# rgb-led_alt.net
KiCad netlist of a schematic drawn in EAGLE
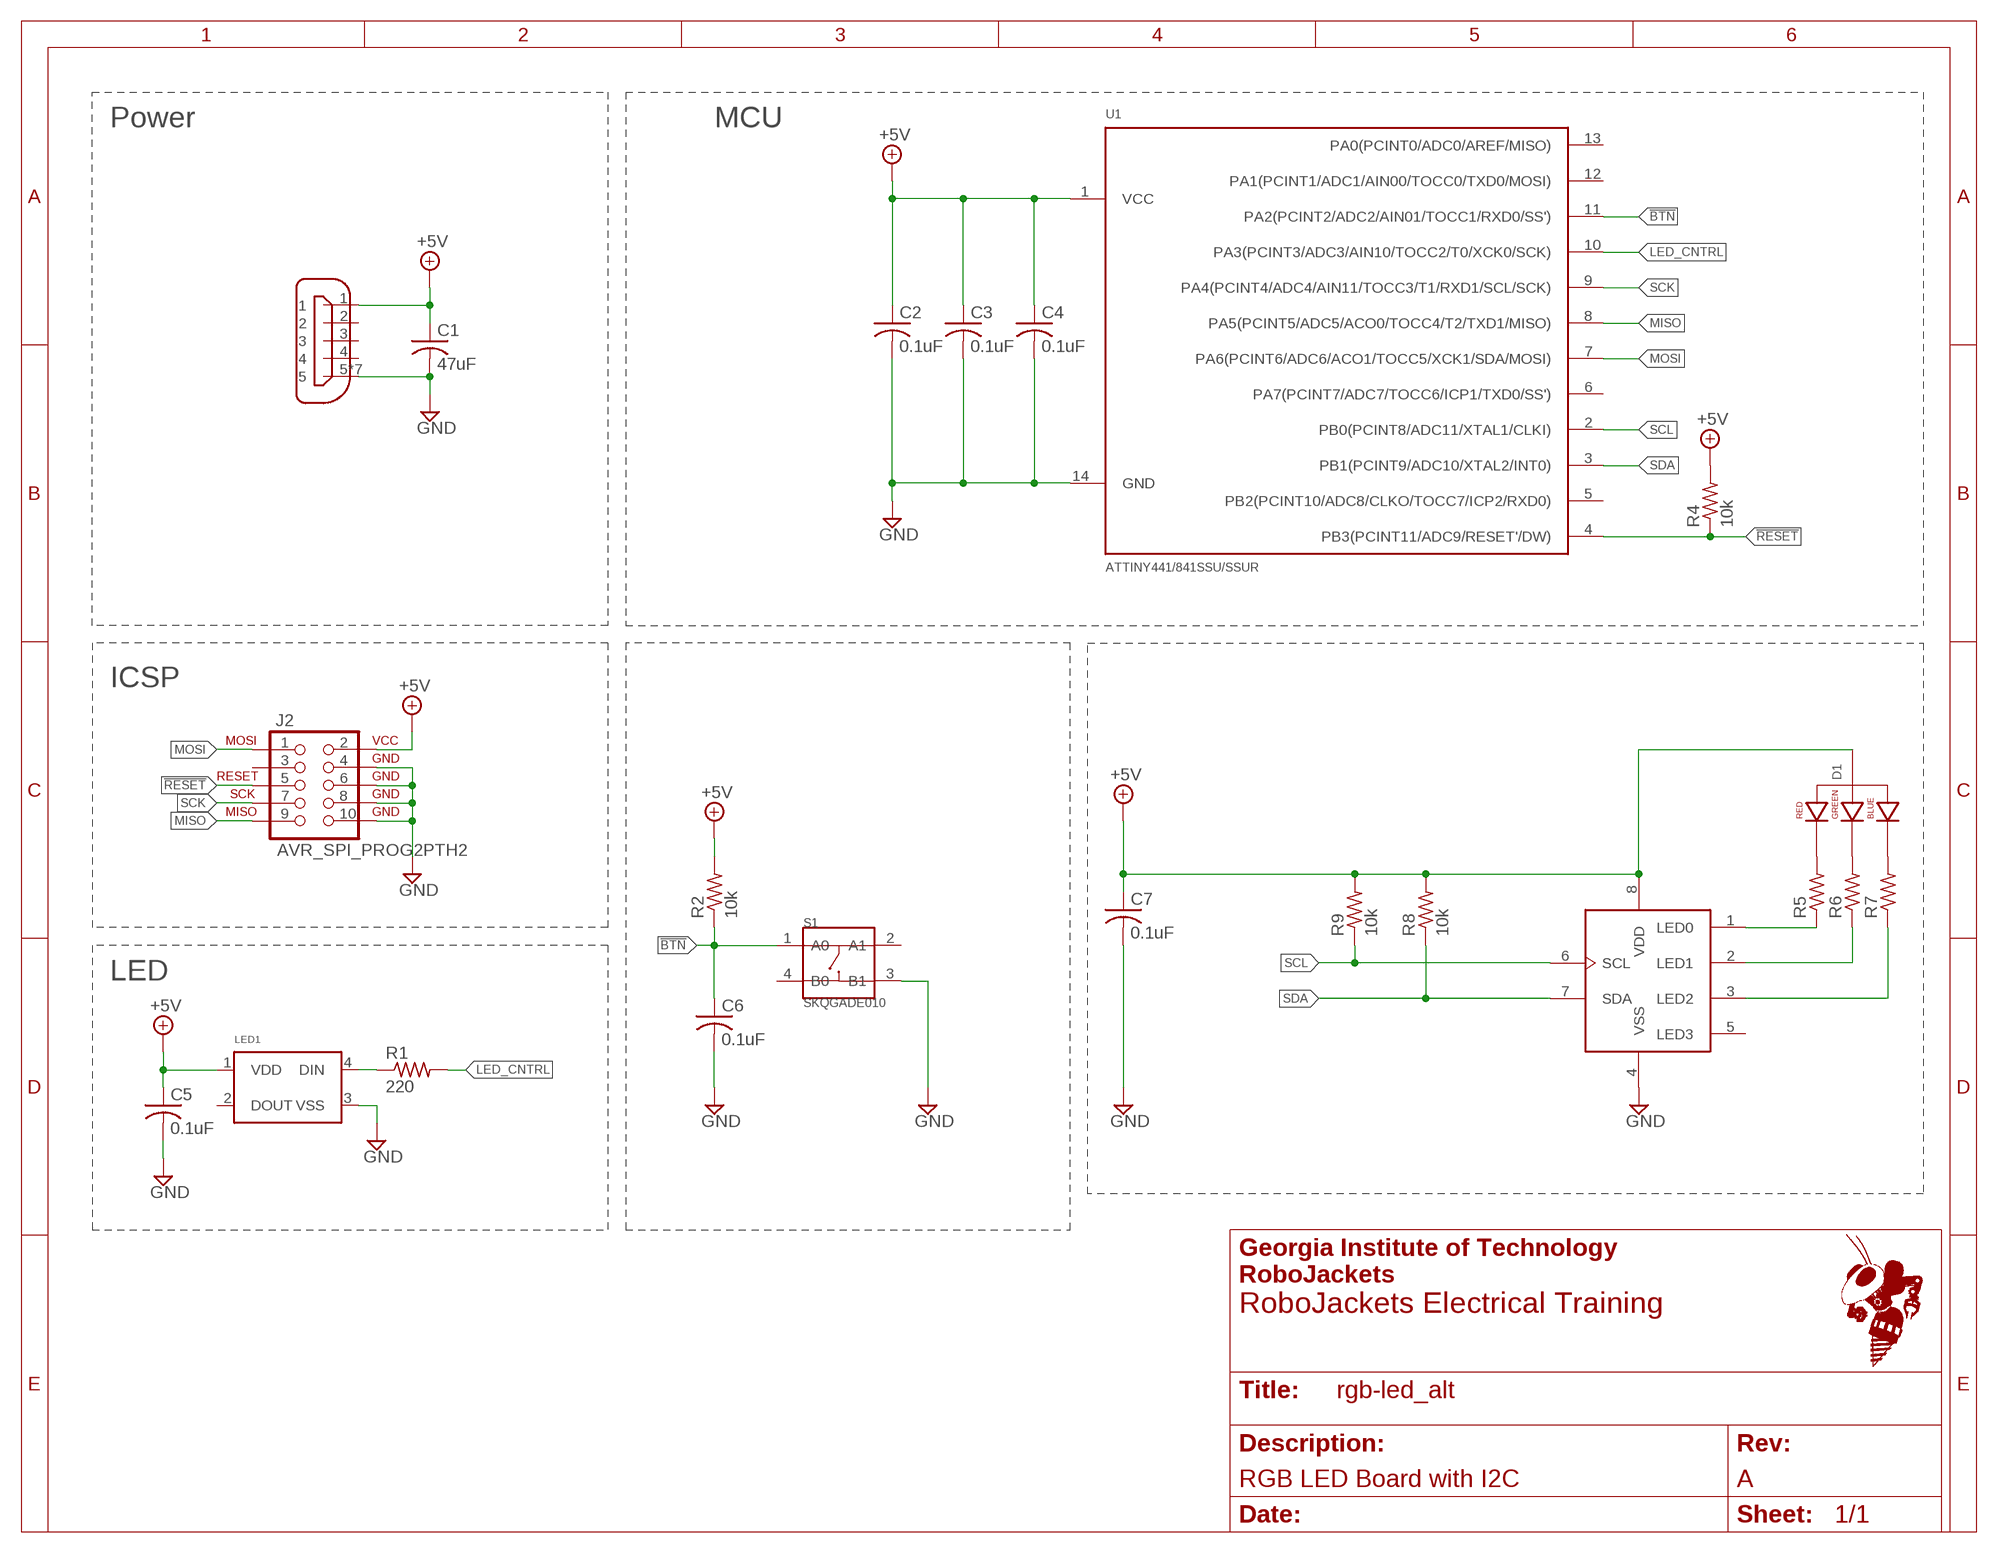
[diagram p0: schematic, sheet 1]

(export (version "E")
  (design (tool "Eeschema 10.0.6"))
  (components
    (comp (ref "C1")
      (value "47uF")
      (footprint "eagle-import:C1206")
      (libsource (lib "eagle-import") (part "C-USC1206"))
    )
    (comp (ref "C2")
      (value "0.1uF")
      (footprint "eagle-import:C0603")
      (libsource (lib "eagle-import") (part "C-USC0603"))
    )
    (comp (ref "C3")
      (value "0.1uF")
      (footprint "eagle-import:C0603")
      (libsource (lib "eagle-import") (part "C-USC0603"))
    )
    (comp (ref "C4")
      (value "0.1uF")
      (footprint "eagle-import:C0603")
      (libsource (lib "eagle-import") (part "C-USC0603"))
    )
    (comp (ref "C5")
      (value "0.1uF")
      (footprint "eagle-import:C0603")
      (libsource (lib "eagle-import") (part "C-USC0603"))
    )
    (comp (ref "C6")
      (value "0.1uF")
      (footprint "eagle-import:C0603")
      (libsource (lib "eagle-import") (part "C-USC0603"))
    )
    (comp (ref "C7")
      (value "0.1uF")
      (footprint "eagle-import:C0603")
      (libsource (lib "eagle-import") (part "C-USC0603"))
    )
    (comp (ref "D1")
      (value "LED-RGB-CA-THRUCLEAR")
      (footprint "eagle-import:LED-RGB-THRU")
      (libsource (lib "eagle-import") (part "LED-RGB-CA-THRUCLEAR"))
    )
    (comp (ref "J1")
      (value "MICRO-USB")
      (footprint "eagle-import:GS-14-2180")
      (libsource (lib "eagle-import") (part "MICRO-USB"))
    )
    (comp (ref "J2")
      (value "AVR_SPI_PROG2PTH2")
      (footprint "eagle-import:2X5-SHROUDED")
      (libsource (lib "eagle-import") (part "AVR_SPI_PROG2PTH2"))
    )
    (comp (ref "LED1")
      (value "WS2812B")
      (footprint "eagle-import:5050")
      (libsource (lib "eagle-import") (part "WS2812B"))
    )
    (comp (ref "R1")
      (value "220")
      (footprint "eagle-import:R0603")
      (libsource (lib "eagle-import") (part "R-US_R0603"))
    )
    (comp (ref "R2")
      (value "10k")
      (footprint "eagle-import:R0603")
      (libsource (lib "eagle-import") (part "resistor_R-US_R0603"))
    )
    (comp (ref "R4")
      (value "10k")
      (footprint "eagle-import:R0603")
      (libsource (lib "eagle-import") (part "resistor_R-US_R0603"))
    )
    (comp (ref "R5")
      (value "R-US_R0603")
      (footprint "eagle-import:R0603")
      (libsource (lib "eagle-import") (part "resistor_R-US_R0603"))
    )
    (comp (ref "R6")
      (value "R-US_R0603")
      (footprint "eagle-import:R0603")
      (libsource (lib "eagle-import") (part "resistor_R-US_R0603"))
    )
    (comp (ref "R7")
      (value "R-US_R0603")
      (footprint "eagle-import:R0603")
      (libsource (lib "eagle-import") (part "resistor_R-US_R0603"))
    )
    (comp (ref "R8")
      (value "10k")
      (footprint "eagle-import:R0603")
      (libsource (lib "eagle-import") (part "resistor_R-US_R0603"))
    )
    (comp (ref "R9")
      (value "10k")
      (footprint "eagle-import:R0603")
      (libsource (lib "eagle-import") (part "resistor_R-US_R0603"))
    )
    (comp (ref "S1")
      (value "SKQGADE010")
      (footprint "eagle-import:SW4-SMD-5.2X5.2X1.5MM")
      (libsource (lib "eagle-import") (part "SMD-SWITCH-TOP-260GF(4P-D5.2MM)"))
    )
    (comp (ref "U1")
      (value "ATTINY441/841SSU/SSUR")
      (footprint "eagle-import:SOIC-14")
      (libsource (lib "eagle-import") (part "ATTINY441/841SSU/SSUR"))
    )
    (comp (ref "U2")
      (value "PCA9533")
      (footprint "eagle-import:SOIC8")
      (libsource (lib "eagle-import") (part "PCA9533"))
    )
  )
  (nets
    (net (code "1") (name "+5V") (class "Default")
      (node (ref "C1") (pin "1") (pinfunction "1_1") (pintype "passive"))
      (node (ref "C2") (pin "1") (pinfunction "1_1") (pintype "passive"))
      (node (ref "C3") (pin "1") (pinfunction "1_1") (pintype "passive"))
      (node (ref "C4") (pin "1") (pinfunction "1_1") (pintype "passive"))
      (node (ref "C5") (pin "1") (pinfunction "1_1") (pintype "passive"))
      (node (ref "C7") (pin "1") (pinfunction "1_1") (pintype "passive"))
      (node (ref "D1") (pin "2") (pinfunction "ANODE_2") (pintype "bidirectional"))
      (node (ref "J1") (pin "1") (pinfunction "1_1") (pintype "bidirectional"))
      (node (ref "J2") (pin "2") (pinfunction "VCC_2") (pintype "power_in"))
      (node (ref "LED1") (pin "1") (pinfunction "VDD_1") (pintype "bidirectional"))
      (node (ref "R2") (pin "2") (pinfunction "2_2") (pintype "passive"))
      (node (ref "R4") (pin "2") (pinfunction "2_2") (pintype "passive"))
      (node (ref "R8") (pin "2") (pinfunction "2_2") (pintype "passive"))
      (node (ref "R9") (pin "2") (pinfunction "2_2") (pintype "passive"))
      (node (ref "U1") (pin "1") (pinfunction "VCC_1") (pintype "bidirectional"))
      (node (ref "U2") (pin "8") (pinfunction "VDD_8") (pintype "power_in"))
    )
    (net (code "2") (name "/~{BTN}") (class "Default")
      (node (ref "C6") (pin "1") (pinfunction "1_1") (pintype "passive"))
      (node (ref "R2") (pin "1") (pinfunction "1_1") (pintype "passive"))
      (node (ref "S1") (pin "1") (pinfunction "A0_1") (pintype "bidirectional"))
      (node (ref "U1") (pin "11") (pinfunction "PA2(PCINT2/ADC2/AIN01/TOCC1/RXD0/SS')_11") (pintype "bidirectional"))
    )
    (net (code "3") (name "/~{RESET}") (class "Default")
      (node (ref "J2") (pin "5") (pinfunction "RESET_5") (pintype "passive"))
      (node (ref "R4") (pin "1") (pinfunction "1_1") (pintype "passive"))
      (node (ref "U1") (pin "4") (pinfunction "PB3(PCINT11/ADC9/RESET'/DW)_4") (pintype "bidirectional"))
    )
    (net (code "4") (name "GND") (class "Default")
      (node (ref "C1") (pin "2") (pinfunction "2_2") (pintype "passive"))
      (node (ref "C2") (pin "2") (pinfunction "2_2") (pintype "passive"))
      (node (ref "C3") (pin "2") (pinfunction "2_2") (pintype "passive"))
      (node (ref "C4") (pin "2") (pinfunction "2_2") (pintype "passive"))
      (node (ref "C5") (pin "2") (pinfunction "2_2") (pintype "passive"))
      (node (ref "C6") (pin "2") (pinfunction "2_2") (pintype "passive"))
      (node (ref "C7") (pin "2") (pinfunction "2_2") (pintype "passive"))
      (node (ref "J1") (pin "5") (pinfunction "5_5") (pintype "bidirectional"))
      (node (ref "J1") (pin "5@1") (pinfunction "5_5@1") (pintype "bidirectional"))
      (node (ref "J1") (pin "5@2") (pinfunction "5_5@2") (pintype "bidirectional"))
      (node (ref "J1") (pin "5@3") (pinfunction "5_5@3") (pintype "bidirectional"))
      (node (ref "J1") (pin "5@4") (pinfunction "5_5@4") (pintype "bidirectional"))
      (node (ref "J1") (pin "5@6") (pinfunction "5_5@6") (pintype "bidirectional"))
      (node (ref "J1") (pin "5@7") (pinfunction "5_5@7") (pintype "bidirectional"))
      (node (ref "J2") (pin "10") (pinfunction "GND_10") (pintype "power_in"))
      (node (ref "J2") (pin "4") (pinfunction "GND_4") (pintype "power_in"))
      (node (ref "J2") (pin "6") (pinfunction "GND_6") (pintype "power_in"))
      (node (ref "J2") (pin "8") (pinfunction "GND_8") (pintype "power_in"))
      (node (ref "LED1") (pin "3") (pinfunction "VSS_3") (pintype "bidirectional"))
      (node (ref "S1") (pin "3") (pinfunction "B1_3") (pintype "bidirectional"))
      (node (ref "U1") (pin "14") (pinfunction "GND_14") (pintype "bidirectional"))
      (node (ref "U2") (pin "4") (pinfunction "VSS_4") (pintype "power_in"))
    )
    (net (code "5") (name "LED_CNTRL") (class "Default")
      (node (ref "R1") (pin "2") (pinfunction "2_2") (pintype "passive"))
      (node (ref "U1") (pin "10") (pinfunction "PA3(PCINT3/ADC3/AIN10/TOCC2/T0/XCK0/SCK)_10") (pintype "bidirectional"))
    )
    (net (code "6") (name "MISO") (class "Default")
      (node (ref "J2") (pin "9") (pinfunction "MISO_9") (pintype "passive"))
      (node (ref "U1") (pin "8") (pinfunction "PA5(PCINT5/ADC5/ACO0/TOCC4/T2/TXD1/MISO)_8") (pintype "bidirectional"))
    )
    (net (code "7") (name "MOSI") (class "Default")
      (node (ref "J2") (pin "1") (pinfunction "MOSI_1") (pintype "passive"))
      (node (ref "U1") (pin "7") (pinfunction "PA6(PCINT6/ADC6/ACO1/TOCC5/XCK1/SDA/MOSI)_7") (pintype "bidirectional"))
    )
    (net (code "8") (name "Net-(D1-BLUE_CATHODE)") (class "Default")
      (node (ref "D1") (pin "4") (pinfunction "BLUE_CATHODE_4") (pintype "bidirectional"))
      (node (ref "R7") (pin "2") (pinfunction "2_2") (pintype "passive"))
    )
    (net (code "9") (name "Net-(D1-GREEN_CATHODE)") (class "Default")
      (node (ref "D1") (pin "3") (pinfunction "GREEN_CATHODE_3") (pintype "bidirectional"))
      (node (ref "R6") (pin "2") (pinfunction "2_2") (pintype "passive"))
    )
    (net (code "10") (name "Net-(D1-RED_CATHODE)") (class "Default")
      (node (ref "D1") (pin "1") (pinfunction "RED_CATHODE_1") (pintype "bidirectional"))
      (node (ref "R5") (pin "2") (pinfunction "2_2") (pintype "passive"))
    )
    (net (code "11") (name "Net-(LED1-DIN)") (class "Default")
      (node (ref "LED1") (pin "4") (pinfunction "DIN_4") (pintype "bidirectional"))
      (node (ref "R1") (pin "1") (pinfunction "1_1") (pintype "passive"))
    )
    (net (code "12") (name "Net-(U2-LED0)") (class "Default")
      (node (ref "R5") (pin "1") (pinfunction "1_1") (pintype "passive"))
      (node (ref "U2") (pin "1") (pinfunction "LED0_1") (pintype "bidirectional"))
    )
    (net (code "13") (name "Net-(U2-LED1)") (class "Default")
      (node (ref "R6") (pin "1") (pinfunction "1_1") (pintype "passive"))
      (node (ref "U2") (pin "2") (pinfunction "LED1_2") (pintype "bidirectional"))
    )
    (net (code "14") (name "Net-(U2-LED2)") (class "Default")
      (node (ref "R7") (pin "1") (pinfunction "1_1") (pintype "passive"))
      (node (ref "U2") (pin "3") (pinfunction "LED2_3") (pintype "bidirectional"))
    )
    (net (code "15") (name "SCK") (class "Default")
      (node (ref "J2") (pin "7") (pinfunction "SCK_7") (pintype "passive"))
      (node (ref "U1") (pin "9") (pinfunction "PA4(PCINT4/ADC4/AIN11/TOCC3/T1/RXD1/SCL/SCK)_9") (pintype "bidirectional"))
    )
    (net (code "16") (name "SCL") (class "Default")
      (node (ref "R9") (pin "1") (pinfunction "1_1") (pintype "passive"))
      (node (ref "U1") (pin "2") (pinfunction "PB0(PCINT8/ADC11/XTAL1/CLKI)_2") (pintype "bidirectional"))
      (node (ref "U2") (pin "6") (pinfunction "SCL_6") (pintype "input"))
    )
    (net (code "17") (name "SDA") (class "Default")
      (node (ref "R8") (pin "1") (pinfunction "1_1") (pintype "passive"))
      (node (ref "U1") (pin "3") (pinfunction "PB1(PCINT9/ADC10/XTAL2/INT0)_3") (pintype "bidirectional"))
      (node (ref "U2") (pin "7") (pinfunction "SDA_7") (pintype "bidirectional"))
    )
    (net (code "18") (name "unconnected-(J1-Pad2)") (class "Default")
      (node (ref "J1") (pin "2") (pinfunction "2_2") (pintype "bidirectional"))
    )
    (net (code "19") (name "unconnected-(J1-Pad3)") (class "Default")
      (node (ref "J1") (pin "3") (pinfunction "3_3") (pintype "bidirectional"))
    )
    (net (code "20") (name "unconnected-(J1-Pad4)") (class "Default")
      (node (ref "J1") (pin "4") (pinfunction "4_4") (pintype "bidirectional"))
    )
    (net (code "21") (name "unconnected-(J2-NC-Pad3)") (class "Default")
      (node (ref "J2") (pin "3") (pinfunction "NC_3") (pintype "no_connect"))
    )
    (net (code "22") (name "unconnected-(LED1-DOUT-Pad2)") (class "Default")
      (node (ref "LED1") (pin "2") (pinfunction "DOUT_2") (pintype "bidirectional"))
    )
    (net (code "23") (name "unconnected-(S1-A1-Pad2)") (class "Default")
      (node (ref "S1") (pin "2") (pinfunction "A1_2") (pintype "bidirectional"))
    )
    (net (code "24") (name "unconnected-(S1-B0-Pad4)") (class "Default")
      (node (ref "S1") (pin "4") (pinfunction "B0_4") (pintype "bidirectional"))
    )
    (net (code "25") (name "unconnected-(U1-PA0(PCINT0{slash}ADC0{slash}AREF{slash}MISO)-Pad13)") (class "Default")
      (node (ref "U1") (pin "13") (pinfunction "PA0(PCINT0/ADC0/AREF/MISO)_13") (pintype "bidirectional"))
    )
    (net (code "26") (name "unconnected-(U1-PA1(PCINT1{slash}ADC1{slash}AIN00{slash}TOCC0{slash}TXD0{slash}MOSI)-Pad12)") (class "Default")
      (node (ref "U1") (pin "12") (pinfunction "PA1(PCINT1/ADC1/AIN00/TOCC0/TXD0/MOSI)_12") (pintype "bidirectional"))
    )
    (net (code "27") (name "unconnected-(U1-PA7(PCINT7{slash}ADC7{slash}TOCC6{slash}ICP1{slash}TXD0{slash}SS')-Pad6)") (class "Default")
      (node (ref "U1") (pin "6") (pinfunction "PA7(PCINT7/ADC7/TOCC6/ICP1/TXD0/SS')_6") (pintype "bidirectional"))
    )
    (net (code "28") (name "unconnected-(U1-PB2(PCINT10{slash}ADC8{slash}CLKO{slash}TOCC7{slash}ICP2{slash}RXD0)-Pad5)") (class "Default")
      (node (ref "U1") (pin "5") (pinfunction "PB2(PCINT10/ADC8/CLKO/TOCC7/ICP2/RXD0)_5") (pintype "bidirectional"))
    )
    (net (code "29") (name "unconnected-(U2-LED3-Pad5)") (class "Default")
      (node (ref "U2") (pin "5") (pinfunction "LED3_5") (pintype "bidirectional"))
    )
  )
)
